# LED.net
KiCad netlist of a schematic drawn in Altium Designer
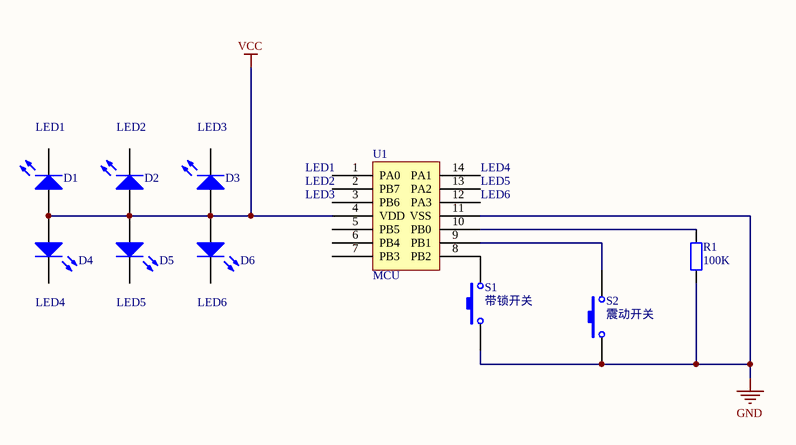
[diagram p0: LED.SchDoc]

(export (version "E")
  (design (tool "Eeschema 10.0.6"))
  (components
    (comp (ref "D1")
      (value "LED")
      (footprint "LED_A1")
      (description "发光二极管")
      (libsource (lib "0.3 - LED发光二极管") (part "LED"))
    )
    (comp (ref "D2")
      (value "LED")
      (footprint "LED_A1")
      (description "发光二极管")
      (libsource (lib "0.3 - LED发光二极管") (part "LED"))
    )
    (comp (ref "D3")
      (value "LED")
      (footprint "LED_A1")
      (description "发光二极管")
      (libsource (lib "0.3 - LED发光二极管") (part "LED"))
    )
    (comp (ref "D4")
      (value "LED")
      (footprint "LED_A1")
      (description "发光二极管")
      (libsource (lib "0.3 - LED发光二极管") (part "LED"))
    )
    (comp (ref "D5")
      (value "LED")
      (footprint "LED_A1")
      (description "发光二极管")
      (libsource (lib "0.3 - LED发光二极管") (part "LED"))
    )
    (comp (ref "D6")
      (value "LED")
      (footprint "LED_A1")
      (description "发光二极管")
      (libsource (lib "0.3 - LED发光二极管") (part "LED"))
    )
    (comp (ref "R1")
      (value "100K")
      (footprint "R 0805_L")
      (description "下拉电阻")
      (fields (field (name "版权归属") "来自淘宝 ID：黄晶宝石"))
      (libsource (lib "0.1 - 电阻-电容-电感") (part "R"))
    )
    (comp (ref "S1")
      (value "带锁开关")
      (footprint "SW_PB2_A1")
      (description "微动开关")
      (fields (field (name "PUBLISHER") "Altium Limited"))
      (libsource (lib "0.7 - 常用按键-开关") (part "SW-PB"))
    )
    (comp (ref "S2")
      (value "震动开关")
      (footprint "SW_PB2_A1")
      (description "微动开关")
      (fields (field (name "PUBLISHER") "Altium Limited"))
      (libsource (lib "0.7 - 常用按键-开关") (part "SW-PB"))
    )
    (comp (ref "U1") (value "MCU") (description "53D_sop14") (libsource (lib "九齐") (part "NY8A053D_SOP14")))
  )
  (nets
    (net (code "1") (name "GND") (class "Default")
      (node (ref "R1") (pin "2") (pinfunction "2_2") (pintype "passive"))
      (node (ref "S1") (pin "1") (pinfunction "1_1") (pintype "passive"))
      (node (ref "S2") (pin "1") (pinfunction "1_1") (pintype "passive"))
      (node (ref "U1") (pin "11") (pinfunction "VSS_11") (pintype "passive"))
    )
    (net (code "2") (name "Net-(U1-PB0)") (class "Default")
      (node (ref "R1") (pin "1") (pinfunction "1_1") (pintype "passive"))
      (node (ref "U1") (pin "10") (pinfunction "PB0_10") (pintype "passive"))
    )
    (net (code "3") (name "Net-(U1-PB1)") (class "Default")
      (node (ref "S2") (pin "2") (pinfunction "2_2") (pintype "passive"))
      (node (ref "U1") (pin "9") (pinfunction "PB1_9") (pintype "passive"))
    )
    (net (code "4") (name "Net-(U1-PB2)") (class "Default")
      (node (ref "S1") (pin "2") (pinfunction "2_2") (pintype "passive"))
      (node (ref "U1") (pin "8") (pinfunction "PB2_8") (pintype "passive"))
    )
    (net (code "5") (name "VCC") (class "Default")
      (node (ref "D1") (pin "1") (pinfunction "A_1") (pintype "passive"))
      (node (ref "D2") (pin "1") (pinfunction "A_1") (pintype "passive"))
      (node (ref "D3") (pin "1") (pinfunction "A_1") (pintype "passive"))
      (node (ref "D4") (pin "1") (pinfunction "A_1") (pintype "passive"))
      (node (ref "D5") (pin "1") (pinfunction "A_1") (pintype "passive"))
      (node (ref "D6") (pin "1") (pinfunction "A_1") (pintype "passive"))
      (node (ref "U1") (pin "4") (pinfunction "VDD_4") (pintype "passive"))
    )
    (net (code "6") (name "unconnected-(D1-K-Pad2)") (class "Default")
      (node (ref "D1") (pin "2") (pinfunction "K_2") (pintype "passive"))
    )
    (net (code "7") (name "unconnected-(D2-K-Pad2)") (class "Default")
      (node (ref "D2") (pin "2") (pinfunction "K_2") (pintype "passive"))
    )
    (net (code "8") (name "unconnected-(D3-K-Pad2)") (class "Default")
      (node (ref "D3") (pin "2") (pinfunction "K_2") (pintype "passive"))
    )
    (net (code "9") (name "unconnected-(D4-K-Pad2)") (class "Default")
      (node (ref "D4") (pin "2") (pinfunction "K_2") (pintype "passive"))
    )
    (net (code "10") (name "unconnected-(D5-K-Pad2)") (class "Default")
      (node (ref "D5") (pin "2") (pinfunction "K_2") (pintype "passive"))
    )
    (net (code "11") (name "unconnected-(D6-K-Pad2)") (class "Default")
      (node (ref "D6") (pin "2") (pinfunction "K_2") (pintype "passive"))
    )
    (net (code "12") (name "unconnected-(U1-PA0-Pad1)") (class "Default")
      (node (ref "U1") (pin "1") (pinfunction "PA0_1") (pintype "passive"))
    )
    (net (code "13") (name "unconnected-(U1-PA1-Pad14)") (class "Default")
      (node (ref "U1") (pin "14") (pinfunction "PA1_14") (pintype "passive"))
    )
    (net (code "14") (name "unconnected-(U1-PA2-Pad13)") (class "Default")
      (node (ref "U1") (pin "13") (pinfunction "PA2_13") (pintype "passive"))
    )
    (net (code "15") (name "unconnected-(U1-PA3-Pad12)") (class "Default")
      (node (ref "U1") (pin "12") (pinfunction "PA3_12") (pintype "passive"))
    )
    (net (code "16") (name "unconnected-(U1-PB3-Pad7)") (class "Default")
      (node (ref "U1") (pin "7") (pinfunction "PB3_7") (pintype "passive"))
    )
    (net (code "17") (name "unconnected-(U1-PB4-Pad6)") (class "Default")
      (node (ref "U1") (pin "6") (pinfunction "PB4_6") (pintype "passive"))
    )
    (net (code "18") (name "unconnected-(U1-PB5-Pad5)") (class "Default")
      (node (ref "U1") (pin "5") (pinfunction "PB5_5") (pintype "passive"))
    )
    (net (code "19") (name "unconnected-(U1-PB6-Pad3)") (class "Default")
      (node (ref "U1") (pin "3") (pinfunction "PB6_3") (pintype "passive"))
    )
    (net (code "20") (name "unconnected-(U1-PB7-Pad2)") (class "Default")
      (node (ref "U1") (pin "2") (pinfunction "PB7_2") (pintype "passive"))
    )
  )
)
